# lickometer_v1_0.net
KiCad netlist of a schematic drawn in EAGLE
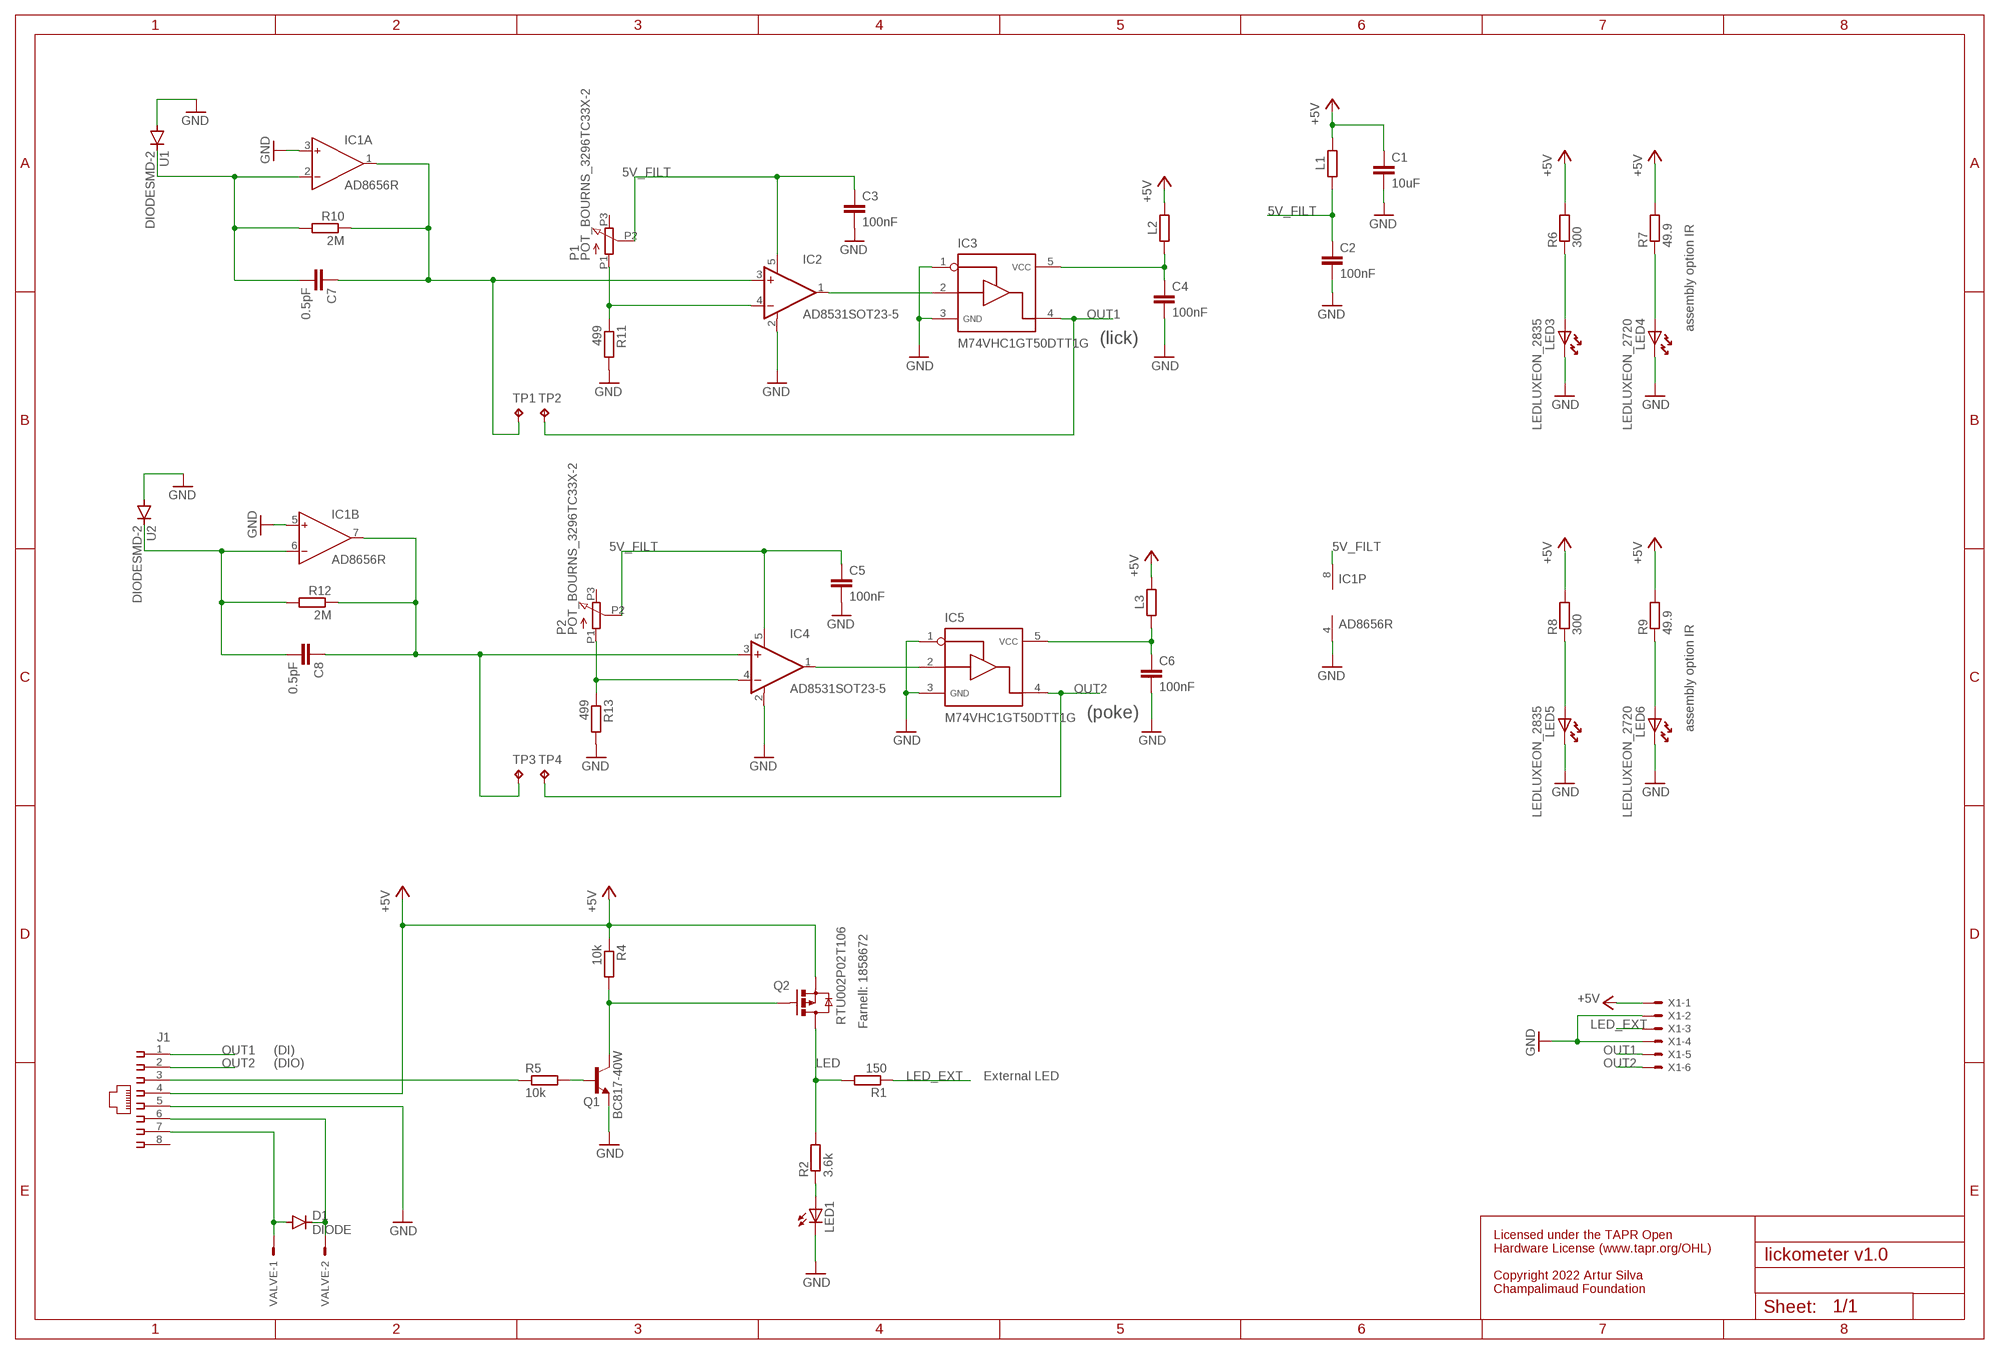
[diagram p0: schematic, sheet 1]

(export (version "E")
  (design (tool "Eeschema 10.0.6"))
  (components
    (comp (ref "C1")
      (value "10uF")
      (footprint "eagle-import:C0603")
      (libsource (lib "eagle-import") (part "C-EUC0603"))
    )
    (comp (ref "C2")
      (value "100nF")
      (footprint "eagle-import:C0402")
      (libsource (lib "eagle-import") (part "C-EUC0402"))
    )
    (comp (ref "C3")
      (value "100nF")
      (footprint "eagle-import:C0402")
      (libsource (lib "eagle-import") (part "C-EUC0402"))
    )
    (comp (ref "C4")
      (value "100nF")
      (footprint "eagle-import:C0402")
      (libsource (lib "eagle-import") (part "C-EUC0402"))
    )
    (comp (ref "C5")
      (value "100nF")
      (footprint "eagle-import:C0402")
      (libsource (lib "eagle-import") (part "C-EUC0402"))
    )
    (comp (ref "C6")
      (value "100nF")
      (footprint "eagle-import:C0402")
      (libsource (lib "eagle-import") (part "C-EUC0402"))
    )
    (comp (ref "C7")
      (value "0.5pF")
      (footprint "eagle-import:C0402")
      (libsource (lib "eagle-import") (part "C-EUC0402"))
    )
    (comp (ref "C8")
      (value "0.5pF")
      (footprint "eagle-import:C0402")
      (libsource (lib "eagle-import") (part "C-EUC0402"))
    )
    (comp (ref "D1")
      (value "DIODE")
      (footprint "eagle-import:SOD-323-DIODE")
      (libsource (lib "eagle-import") (part "DIODE"))
    )
    (comp (ref "IC1")
      (value "AD8656R")
      (footprint "eagle-import:SO8")
      (fields (field (name "MPN") "AD8656ARZ"))
      (libsource (lib "eagle-import") (part "AD8656R"))
    )
    (comp (ref "IC2")
      (value "AD8531SOT23-5")
      (footprint "eagle-import:SOT23-5")
      (libsource (lib "eagle-import") (part "AD8531SOT23-5"))
    )
    (comp (ref "IC3")
      (value "M74VHC1GT50DTT1G")
      (footprint "eagle-import:SOT23-5")
      (libsource (lib "eagle-import") (part "SN74LVC1G125"))
    )
    (comp (ref "IC4")
      (value "AD8531SOT23-5")
      (footprint "eagle-import:SOT23-5")
      (libsource (lib "eagle-import") (part "AD8531SOT23-5"))
    )
    (comp (ref "IC5")
      (value "M74VHC1GT50DTT1G")
      (footprint "eagle-import:SOT23-5")
      (libsource (lib "eagle-import") (part "SN74LVC1G125"))
    )
    (comp (ref "J1")
      (value "215878-2")
      (footprint "eagle-import:215878-2")
      (libsource (lib "eagle-import") (part "215878-2"))
    )
    (comp (ref "L1")
      (value "1k@100M")
      (footprint "eagle-import:R0402")
      (libsource (lib "eagle-import") (part "R-EU_R0402"))
    )
    (comp (ref "L2")
      (value "1k@100M")
      (footprint "eagle-import:R0402")
      (libsource (lib "eagle-import") (part "R-EU_R0402"))
    )
    (comp (ref "L3")
      (value "1k@100M")
      (footprint "eagle-import:R0402")
      (libsource (lib "eagle-import") (part "R-EU_R0402"))
    )
    (comp (ref "LED1")
      (value "LED3MM")
      (footprint "eagle-import:LED3MM")
      (libsource (lib "eagle-import") (part "LED3MM"))
    )
    (comp (ref "LED3")
      (value "LEDLUXEON_2835")
      (footprint "eagle-import:LED_LUXEON_2835")
      (libsource (lib "eagle-import") (part "LEDLUXEON_2835"))
    )
    (comp (ref "LED4")
      (value "LEDLUXEON_2720")
      (footprint "eagle-import:LED_LUXEON_2720")
      (libsource (lib "eagle-import") (part "LEDLUXEON_2720"))
    )
    (comp (ref "LED5")
      (value "LEDLUXEON_2835")
      (footprint "eagle-import:LED_LUXEON_2835")
      (libsource (lib "eagle-import") (part "LEDLUXEON_2835"))
    )
    (comp (ref "LED6")
      (value "LEDLUXEON_2720")
      (footprint "eagle-import:LED_LUXEON_2720")
      (libsource (lib "eagle-import") (part "LEDLUXEON_2720"))
    )
    (comp (ref "P1")
      (value "POT_BOURNS_3296TC33X-2")
      (footprint "eagle-import:POT-TC33X-2")
      (libsource (lib "eagle-import") (part "POT_BOURNS_3296TC33X-2"))
    )
    (comp (ref "P2")
      (value "POT_BOURNS_3296TC33X-2")
      (footprint "eagle-import:POT-TC33X-2")
      (libsource (lib "eagle-import") (part "POT_BOURNS_3296TC33X-2"))
    )
    (comp (ref "Q1")
      (value "BC817-40W")
      (footprint "eagle-import:SOT323-BEC")
      (libsource (lib "eagle-import") (part "BC817"))
    )
    (comp (ref "Q2")
      (value "RTU002P02T106")
      (footprint "eagle-import:SOT323")
      (libsource (lib "eagle-import") (part "MOSFET-PCHANNEL-ROHM"))
    )
    (comp (ref "R1")
      (value "150")
      (footprint "eagle-import:R0402")
      (libsource (lib "eagle-import") (part "R-EU_R0402"))
    )
    (comp (ref "R2")
      (value "3.6k")
      (footprint "eagle-import:R0402")
      (libsource (lib "eagle-import") (part "R-EU_R0402"))
    )
    (comp (ref "R4")
      (value "10k")
      (footprint "eagle-import:R0402")
      (libsource (lib "eagle-import") (part "R-EU_R0402"))
    )
    (comp (ref "R5")
      (value "10k")
      (footprint "eagle-import:R0402")
      (libsource (lib "eagle-import") (part "R-EU_R0402"))
    )
    (comp (ref "R6")
      (value "300")
      (footprint "eagle-import:R0805")
      (libsource (lib "eagle-import") (part "R-EU_R0805"))
    )
    (comp (ref "R7")
      (value "49.9")
      (footprint "eagle-import:R0805")
      (libsource (lib "eagle-import") (part "R-EU_R0805"))
    )
    (comp (ref "R8")
      (value "300")
      (footprint "eagle-import:R0805")
      (libsource (lib "eagle-import") (part "R-EU_R0805"))
    )
    (comp (ref "R9")
      (value "49.9")
      (footprint "eagle-import:R0805")
      (libsource (lib "eagle-import") (part "R-EU_R0805"))
    )
    (comp (ref "R10")
      (value "2M")
      (footprint "eagle-import:R0402")
      (libsource (lib "eagle-import") (part "R-EU_R0402"))
    )
    (comp (ref "R11")
      (value "499")
      (footprint "eagle-import:R0402")
      (libsource (lib "eagle-import") (part "R-EU_R0402"))
    )
    (comp (ref "R12")
      (value "2M")
      (footprint "eagle-import:R0402")
      (libsource (lib "eagle-import") (part "R-EU_R0402"))
    )
    (comp (ref "R13")
      (value "499")
      (footprint "eagle-import:R0402")
      (libsource (lib "eagle-import") (part "R-EU_R0402"))
    )
    (comp (ref "TP1")
      (value "TPTP08SQ")
      (footprint "eagle-import:TP08SQ")
      (libsource (lib "eagle-import") (part "TPTP08SQ"))
    )
    (comp (ref "TP2")
      (value "TPTP08SQ")
      (footprint "eagle-import:TP08SQ")
      (libsource (lib "eagle-import") (part "TPTP08SQ"))
    )
    (comp (ref "TP3")
      (value "TPTP08SQ")
      (footprint "eagle-import:TP08SQ")
      (libsource (lib "eagle-import") (part "TPTP08SQ"))
    )
    (comp (ref "TP4")
      (value "TPTP08SQ")
      (footprint "eagle-import:TP08SQ")
      (libsource (lib "eagle-import") (part "TPTP08SQ"))
    )
    (comp (ref "U1")
      (value "DIODESMD-2")
      (footprint "eagle-import:SMD-2")
      (libsource (lib "eagle-import") (part "DIODESMD-2"))
    )
    (comp (ref "U2")
      (value "DIODESMD-2")
      (footprint "eagle-import:SMD-2")
      (libsource (lib "eagle-import") (part "DIODESMD-2"))
    )
    (comp (ref "VALVE")
      (value "22-23-2021")
      (footprint "eagle-import:22-23-2021")
      (fields (field (name "MF") "MOLEX"))
      (libsource (lib "eagle-import") (part "22-23-2021"))
    )
    (comp (ref "X1")
      (value "22-23-2061")
      (footprint "eagle-import:22-23-2061")
      (fields (field (name "MF") "MOLEX"))
      (libsource (lib "eagle-import") (part "22-23-2061"))
    )
  )
  (nets
    (net (code "1") (name "+5V") (class "Default")
      (node (ref "C1") (pin "1") (pinfunction "1_1") (pintype "passive"))
      (node (ref "J1") (pin "4") (pinfunction "4_4") (pintype "passive"))
      (node (ref "L1") (pin "1") (pinfunction "1_1") (pintype "passive"))
      (node (ref "L2") (pin "2") (pinfunction "2_2") (pintype "passive"))
      (node (ref "L3") (pin "2") (pinfunction "2_2") (pintype "passive"))
      (node (ref "Q2") (pin "1") (pinfunction "S_1") (pintype "passive"))
      (node (ref "R4") (pin "1") (pinfunction "1_1") (pintype "passive"))
      (node (ref "R6") (pin "2") (pinfunction "2_2") (pintype "passive"))
      (node (ref "R7") (pin "2") (pinfunction "2_2") (pintype "passive"))
      (node (ref "R8") (pin "2") (pinfunction "2_2") (pintype "passive"))
      (node (ref "R9") (pin "2") (pinfunction "2_2") (pintype "passive"))
      (node (ref "X1") (pin "1") (pinfunction "S_1") (pintype "passive"))
    )
    (net (code "2") (name "/5V_FILT") (class "Default")
      (node (ref "C2") (pin "1") (pinfunction "1_1") (pintype "passive"))
      (node (ref "C3") (pin "1") (pinfunction "1_1") (pintype "passive"))
      (node (ref "C5") (pin "1") (pinfunction "1_1") (pintype "passive"))
      (node (ref "IC1") (pin "8") (pinfunction "V+_8") (pintype "power_in"))
      (node (ref "IC2") (pin "5") (pinfunction "V+_5") (pintype "power_in"))
      (node (ref "IC4") (pin "5") (pinfunction "V+_5") (pintype "power_in"))
      (node (ref "L1") (pin "2") (pinfunction "2_2") (pintype "passive"))
      (node (ref "P1") (pin "P2") (pinfunction "S_P2") (pintype "passive"))
      (node (ref "P2") (pin "P2") (pinfunction "S_P2") (pintype "passive"))
    )
    (net (code "3") (name "/LED") (class "Default")
      (node (ref "Q2") (pin "3") (pinfunction "D_3") (pintype "passive"))
      (node (ref "R1") (pin "2") (pinfunction "2_2") (pintype "passive"))
      (node (ref "R2") (pin "2") (pinfunction "2_2") (pintype "passive"))
    )
    (net (code "4") (name "/LED_EXT") (class "Default")
      (node (ref "R1") (pin "1") (pinfunction "1_1") (pintype "passive"))
      (node (ref "X1") (pin "3") (pinfunction "S_3") (pintype "passive"))
    )
    (net (code "5") (name "/OUT1") (class "Default")
      (node (ref "IC3") (pin "4") (pinfunction "P$4_4") (pintype "bidirectional"))
      (node (ref "J1") (pin "1") (pinfunction "1_1") (pintype "passive"))
      (node (ref "TP2") (pin "TP") (pinfunction "TP_TP") (pintype "input"))
      (node (ref "X1") (pin "5") (pinfunction "S_5") (pintype "passive"))
    )
    (net (code "6") (name "/OUT2") (class "Default")
      (node (ref "IC5") (pin "4") (pinfunction "P$4_4") (pintype "bidirectional"))
      (node (ref "J1") (pin "2") (pinfunction "2_2") (pintype "passive"))
      (node (ref "TP4") (pin "TP") (pinfunction "TP_TP") (pintype "input"))
      (node (ref "X1") (pin "6") (pinfunction "S_6") (pintype "passive"))
    )
    (net (code "7") (name "GND") (class "Default")
      (node (ref "C1") (pin "2") (pinfunction "2_2") (pintype "passive"))
      (node (ref "C2") (pin "2") (pinfunction "2_2") (pintype "passive"))
      (node (ref "C3") (pin "2") (pinfunction "2_2") (pintype "passive"))
      (node (ref "C4") (pin "2") (pinfunction "2_2") (pintype "passive"))
      (node (ref "C5") (pin "2") (pinfunction "2_2") (pintype "passive"))
      (node (ref "C6") (pin "2") (pinfunction "2_2") (pintype "passive"))
      (node (ref "IC1") (pin "3") (pinfunction "IN+_3") (pintype "input"))
      (node (ref "IC1") (pin "4") (pinfunction "V-_4") (pintype "power_in"))
      (node (ref "IC1") (pin "5") (pinfunction "IN+_5") (pintype "input"))
      (node (ref "IC2") (pin "2") (pinfunction "V-_2") (pintype "power_in"))
      (node (ref "IC3") (pin "1") (pinfunction "P$1_1") (pintype "bidirectional"))
      (node (ref "IC3") (pin "3") (pinfunction "P$3_3") (pintype "bidirectional"))
      (node (ref "IC4") (pin "2") (pinfunction "V-_2") (pintype "power_in"))
      (node (ref "IC5") (pin "1") (pinfunction "P$1_1") (pintype "bidirectional"))
      (node (ref "IC5") (pin "3") (pinfunction "P$3_3") (pintype "bidirectional"))
      (node (ref "J1") (pin "5") (pinfunction "5_5") (pintype "passive"))
      (node (ref "LED1") (pin "K") (pinfunction "C_K") (pintype "passive"))
      (node (ref "LED3") (pin "KATHODE") (pinfunction "K_KATHODE") (pintype "bidirectional"))
      (node (ref "LED4") (pin "KATHODE") (pinfunction "K_KATHODE") (pintype "bidirectional"))
      (node (ref "LED5") (pin "KATHODE") (pinfunction "K_KATHODE") (pintype "bidirectional"))
      (node (ref "LED6") (pin "KATHODE") (pinfunction "K_KATHODE") (pintype "bidirectional"))
      (node (ref "Q1") (pin "E") (pinfunction "E_E") (pintype "passive"))
      (node (ref "R11") (pin "2") (pinfunction "2_2") (pintype "passive"))
      (node (ref "R13") (pin "2") (pinfunction "2_2") (pintype "passive"))
      (node (ref "U1") (pin "A") (pinfunction "A_A") (pintype "passive"))
      (node (ref "U2") (pin "A") (pinfunction "A_A") (pintype "passive"))
      (node (ref "X1") (pin "2") (pinfunction "S_2") (pintype "passive"))
      (node (ref "X1") (pin "4") (pinfunction "S_4") (pintype "passive"))
    )
    (net (code "8") (name "Net-(IC1A-IN-)") (class "Default")
      (node (ref "C7") (pin "2") (pinfunction "2_2") (pintype "passive"))
      (node (ref "IC1") (pin "2") (pinfunction "IN-_2") (pintype "input"))
      (node (ref "R10") (pin "2") (pinfunction "2_2") (pintype "passive"))
      (node (ref "U1") (pin "C") (pinfunction "C_C") (pintype "passive"))
    )
    (net (code "9") (name "Net-(IC1A-OUT)") (class "Default")
      (node (ref "C7") (pin "1") (pinfunction "1_1") (pintype "passive"))
      (node (ref "IC1") (pin "1") (pinfunction "OUT_1") (pintype "output"))
      (node (ref "IC2") (pin "3") (pinfunction "+IN_3") (pintype "input"))
      (node (ref "R10") (pin "1") (pinfunction "1_1") (pintype "passive"))
      (node (ref "TP1") (pin "TP") (pinfunction "TP_TP") (pintype "input"))
    )
    (net (code "10") (name "Net-(IC1B-IN-)") (class "Default")
      (node (ref "C8") (pin "2") (pinfunction "2_2") (pintype "passive"))
      (node (ref "IC1") (pin "6") (pinfunction "IN-_6") (pintype "input"))
      (node (ref "R12") (pin "2") (pinfunction "2_2") (pintype "passive"))
      (node (ref "U2") (pin "C") (pinfunction "C_C") (pintype "passive"))
    )
    (net (code "11") (name "Net-(IC1B-OUT)") (class "Default")
      (node (ref "C8") (pin "1") (pinfunction "1_1") (pintype "passive"))
      (node (ref "IC1") (pin "7") (pinfunction "OUT_7") (pintype "output"))
      (node (ref "IC4") (pin "3") (pinfunction "+IN_3") (pintype "input"))
      (node (ref "R12") (pin "1") (pinfunction "1_1") (pintype "passive"))
      (node (ref "TP3") (pin "TP") (pinfunction "TP_TP") (pintype "input"))
    )
    (net (code "12") (name "Net-(IC2--IN)") (class "Default")
      (node (ref "IC2") (pin "4") (pinfunction "-IN_4") (pintype "input"))
      (node (ref "P1") (pin "P1") (pinfunction "A_P1") (pintype "passive"))
      (node (ref "R11") (pin "1") (pinfunction "1_1") (pintype "passive"))
    )
    (net (code "13") (name "Net-(IC2-OUT)") (class "Default")
      (node (ref "IC2") (pin "1") (pinfunction "OUT_1") (pintype "output"))
      (node (ref "IC3") (pin "2") (pinfunction "P$2_2") (pintype "bidirectional"))
    )
    (net (code "14") (name "Net-(IC3-P$5)") (class "Default")
      (node (ref "C4") (pin "1") (pinfunction "1_1") (pintype "passive"))
      (node (ref "IC3") (pin "5") (pinfunction "P$5_5") (pintype "bidirectional"))
      (node (ref "L2") (pin "1") (pinfunction "1_1") (pintype "passive"))
    )
    (net (code "15") (name "Net-(IC4--IN)") (class "Default")
      (node (ref "IC4") (pin "4") (pinfunction "-IN_4") (pintype "input"))
      (node (ref "P2") (pin "P1") (pinfunction "A_P1") (pintype "passive"))
      (node (ref "R13") (pin "1") (pinfunction "1_1") (pintype "passive"))
    )
    (net (code "16") (name "Net-(IC4-OUT)") (class "Default")
      (node (ref "IC4") (pin "1") (pinfunction "OUT_1") (pintype "output"))
      (node (ref "IC5") (pin "2") (pinfunction "P$2_2") (pintype "bidirectional"))
    )
    (net (code "17") (name "Net-(IC5-P$5)") (class "Default")
      (node (ref "C6") (pin "1") (pinfunction "1_1") (pintype "passive"))
      (node (ref "IC5") (pin "5") (pinfunction "P$5_5") (pintype "bidirectional"))
      (node (ref "L3") (pin "1") (pinfunction "1_1") (pintype "passive"))
    )
    (net (code "18") (name "Net-(J1-Pad3)") (class "Default")
      (node (ref "J1") (pin "3") (pinfunction "3_3") (pintype "passive"))
      (node (ref "R5") (pin "1") (pinfunction "1_1") (pintype "passive"))
    )
    (net (code "19") (name "Net-(LED1-PadA)") (class "Default")
      (node (ref "LED1") (pin "A") (pinfunction "A_A") (pintype "passive"))
      (node (ref "R2") (pin "1") (pinfunction "1_1") (pintype "passive"))
    )
    (net (code "20") (name "Net-(LED3-A)") (class "Default")
      (node (ref "LED3") (pin "ANODE") (pinfunction "A_ANODE") (pintype "bidirectional"))
      (node (ref "R6") (pin "1") (pinfunction "1_1") (pintype "passive"))
    )
    (net (code "21") (name "Net-(LED4-A)") (class "Default")
      (node (ref "LED4") (pin "ANODE") (pinfunction "A_ANODE") (pintype "bidirectional"))
      (node (ref "R7") (pin "1") (pinfunction "1_1") (pintype "passive"))
    )
    (net (code "22") (name "Net-(LED5-A)") (class "Default")
      (node (ref "LED5") (pin "ANODE") (pinfunction "A_ANODE") (pintype "bidirectional"))
      (node (ref "R8") (pin "1") (pinfunction "1_1") (pintype "passive"))
    )
    (net (code "23") (name "Net-(LED6-A)") (class "Default")
      (node (ref "LED6") (pin "ANODE") (pinfunction "A_ANODE") (pintype "bidirectional"))
      (node (ref "R9") (pin "1") (pinfunction "1_1") (pintype "passive"))
    )
    (net (code "24") (name "Net-(Q1-PadB)") (class "Default")
      (node (ref "Q1") (pin "B") (pinfunction "B_B") (pintype "passive"))
      (node (ref "R5") (pin "2") (pinfunction "2_2") (pintype "passive"))
    )
    (net (code "25") (name "Net-(Q2-G)") (class "Default")
      (node (ref "Q1") (pin "C") (pinfunction "C_C") (pintype "passive"))
      (node (ref "Q2") (pin "2") (pinfunction "G_2") (pintype "passive"))
      (node (ref "R4") (pin "2") (pinfunction "2_2") (pintype "passive"))
    )
    (net (code "26") (name "Net-(VALVEA-S)") (class "Default")
      (node (ref "D1") (pin "A") (pinfunction "A_A") (pintype "passive"))
      (node (ref "J1") (pin "7") (pinfunction "7_7") (pintype "passive"))
      (node (ref "VALVE") (pin "1") (pinfunction "S_1") (pintype "passive"))
    )
    (net (code "27") (name "Net-(VALVEB-S)") (class "Default")
      (node (ref "D1") (pin "C") (pinfunction "C_C") (pintype "passive"))
      (node (ref "J1") (pin "6") (pinfunction "6_6") (pintype "passive"))
      (node (ref "VALVE") (pin "2") (pinfunction "S_2") (pintype "passive"))
    )
    (net (code "28") (name "unconnected-(J1-Pad8)") (class "Default")
      (node (ref "J1") (pin "8") (pinfunction "8_8") (pintype "passive"))
    )
    (net (code "29") (name "unconnected-(P1-E-PadP3)") (class "Default")
      (node (ref "P1") (pin "P3") (pinfunction "E_P3") (pintype "passive"))
    )
    (net (code "30") (name "unconnected-(P2-E-PadP3)") (class "Default")
      (node (ref "P2") (pin "P3") (pinfunction "E_P3") (pintype "passive"))
    )
  )
)
